# 03_PCM5102A.net
KiCad netlist of a schematic drawn in Altium Designer
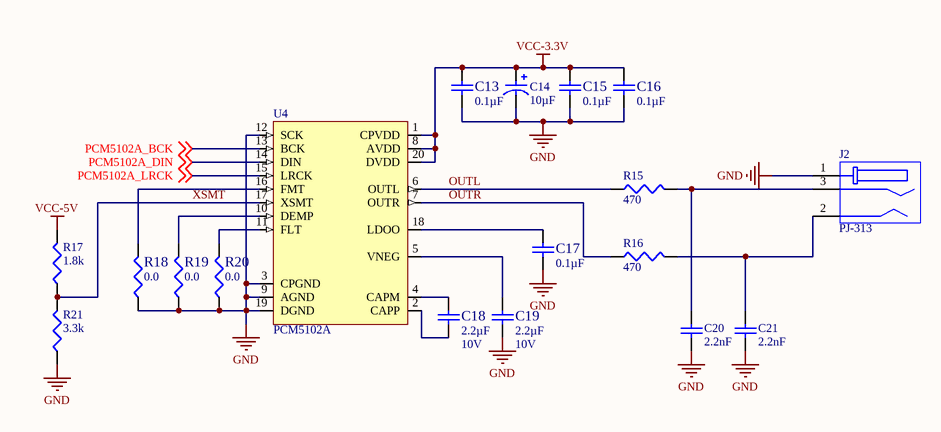
[diagram p0: 03_PCM5102A.SchDoc]

(export (version "E")
  (design (tool "Eeschema 10.0.6"))
  (components
    (comp (ref "C13")
      (value "CC0603KRX7R9BB104")
      (footprint "RAD-0.1")
      (description "CAP CER 0.1UF 50V 10% X7R 0603")
      (fields
        (field (name "MANUFACTURER") "Yageo")
        (field (name "TOLERANCE") "±10%")
        (field (name "CAPACITANCE") "0.1µF")
      )
      (libsource (lib "SEAL_Capacitors_0603") (part "CC0603KRX7R9BB104"))
    )
    (comp (ref "C14")
      (value "EEE-1HA100WR")
      (footprint "RB2-5")
      (description "CAP ALUM 10UF 50V 20% SMD")
      (fields
        (field (name "MANUFACTURER") "Panasonic Electronic Components")
        (field (name "TOLERANCE") "±20%")
        (field (name "CAPACITANCE") "10µF")
      )
      (libsource (lib "DSS_Passives") (part "EEE-1HA100WR"))
    )
    (comp (ref "C15")
      (value "CC0603KRX7R9BB104")
      (footprint "RAD-0.1")
      (description "CAP CER 0.1UF 50V 10% X7R 0603")
      (fields
        (field (name "MANUFACTURER") "Yageo")
        (field (name "TOLERANCE") "±10%")
        (field (name "CAPACITANCE") "0.1µF")
      )
      (libsource (lib "SEAL_Capacitors_0603") (part "CC0603KRX7R9BB104"))
    )
    (comp (ref "C16")
      (value "CC0603KRX7R9BB104")
      (footprint "RAD-0.1")
      (description "CAP CER 0.1UF 50V 10% X7R 0603")
      (fields
        (field (name "MANUFACTURER") "Yageo")
        (field (name "TOLERANCE") "±10%")
        (field (name "CAPACITANCE") "0.1µF")
      )
      (libsource (lib "SEAL_Capacitors_0603") (part "CC0603KRX7R9BB104"))
    )
    (comp (ref "C17")
      (value "CC0603KRX7R9BB104")
      (footprint "RAD-0.1")
      (description "CAP CER 0.1UF 50V 10% X7R 0603")
      (fields
        (field (name "MANUFACTURER") "Yageo")
        (field (name "TOLERANCE") "±10%")
        (field (name "CAPACITANCE") "0.1µF")
      )
      (libsource (lib "SEAL_Capacitors_0603") (part "CC0603KRX7R9BB104"))
    )
    (comp (ref "C18")
      (value "LMK107B7225KA-T")
      (footprint "RB2-5")
      (description "CAP CER 2.2UF 10V 10% X7R 0603")
      (fields
        (field (name "MANUFACTURER") "Taiyo Yuden")
        (field (name "TOLERANCE") "±10%")
        (field (name "CAPACITANCE") "2.2µF")
        (field (name "VOLTAGE - RATED") "10V")
      )
      (libsource (lib "SEAL_Capacitors_0603") (part "LMK107B7225KA-T"))
    )
    (comp (ref "C19")
      (value "LMK107B7225KA-T")
      (footprint "RB2-5")
      (description "CAP CER 2.2UF 10V 10% X7R 0603")
      (fields
        (field (name "MANUFACTURER") "Taiyo Yuden")
        (field (name "TOLERANCE") "±10%")
        (field (name "CAPACITANCE") "2.2µF")
        (field (name "VOLTAGE - RATED") "10V")
      )
      (libsource (lib "SEAL_Capacitors_0603") (part "LMK107B7225KA-T"))
    )
    (comp (ref "C20")
      (value "2.2nF")
      (footprint "RAD-0.1")
      (description "CAP CER 2200PF 50V 10% X7R 0603")
      (fields
        (field (name "MANUFACTURER") "Kemet")
        (field (name "MANUFACTURER PART NUMBER") "C0603C222K5RACTU")
      )
      (libsource (lib "SEAL_Capacitors_0603") (part "C0603C222K5RACTU"))
    )
    (comp (ref "C21")
      (value "2.2nF")
      (footprint "RAD-0.1")
      (description "CAP CER 2200PF 50V 10% X7R 0603")
      (fields
        (field (name "MANUFACTURER") "Kemet")
        (field (name "MANUFACTURER PART NUMBER") "C0603C222K5RACTU")
      )
      (libsource (lib "SEAL_Capacitors_0603") (part "C0603C222K5RACTU"))
    )
    (comp (ref "J2")
      (value "PJ-313")
      (footprint "PJ-313")
      (description "3.5mm Audio Jack")
      (libsource (lib "Miscellaneous Modules") (part "PJ-313"))
    )
    (comp (ref "R15")
      (value "ERJ-3EKF4700V")
      (footprint "AXIAL-0.3")
      (description "RES 470 OHM 1% 1/10W 0603 SMD")
      (fields
        (field (name "MANUFACTURER") "Panasonic Electronic Components")
        (field (name "TOLERANCE") "±1%")
        (field (name "RESISTANCE (OHMS)") "470")
      )
      (libsource (lib "SEAL_Resistors_0603") (part "ERJ-3EKF4700V"))
    )
    (comp (ref "R16")
      (value "ERJ-3EKF4700V")
      (footprint "AXIAL-0.3")
      (description "RES 470 OHM 1% 1/10W 0603 SMD")
      (fields
        (field (name "MANUFACTURER") "Panasonic Electronic Components")
        (field (name "TOLERANCE") "±1%")
        (field (name "RESISTANCE (OHMS)") "470")
      )
      (libsource (lib "SEAL_Resistors_0603") (part "ERJ-3EKF4700V"))
    )
    (comp (ref "R17")
      (value "ERJ-3GEYJ182V")
      (footprint "AXIAL-0.3")
      (description "RES 1.8K OHM 1/10W 5% 0603 SMD")
      (fields
        (field (name "MANUFACTURER") "Panasonic Electronic Components")
        (field (name "TOLERANCE") "±5%")
        (field (name "RESISTANCE (OHMS)") "1.8k")
      )
      (libsource (lib "SEAL_Resistors_0603") (part "ERJ-3GEYJ182V"))
    )
    (comp (ref "R18")
      (value "RC0603JR-070RL")
      (footprint "AXIAL-0.3")
      (description "RES 0.0 OHM 1/10W 0603 SMD")
      (fields
        (field (name "MANUFACTURER") "Yageo")
        (field (name "TOLERANCE") "Jumper")
        (field (name "RESISTANCE (OHMS)") "0.0")
      )
      (libsource (lib "SEAL_Resistors_0603") (part "RC0603JR-070RL"))
    )
    (comp (ref "R19")
      (value "RC0603JR-070RL")
      (footprint "AXIAL-0.3")
      (description "RES 0.0 OHM 1/10W 0603 SMD")
      (fields
        (field (name "MANUFACTURER") "Yageo")
        (field (name "TOLERANCE") "Jumper")
        (field (name "RESISTANCE (OHMS)") "0.0")
      )
      (libsource (lib "SEAL_Resistors_0603") (part "RC0603JR-070RL"))
    )
    (comp (ref "R20")
      (value "RC0603JR-070RL")
      (footprint "AXIAL-0.3")
      (description "RES 0.0 OHM 1/10W 0603 SMD")
      (fields
        (field (name "MANUFACTURER") "Yageo")
        (field (name "TOLERANCE") "Jumper")
        (field (name "RESISTANCE (OHMS)") "0.0")
      )
      (libsource (lib "SEAL_Resistors_0603") (part "RC0603JR-070RL"))
    )
    (comp (ref "R21")
      (value "ERJ-3GEYJ332V")
      (footprint "AXIAL-0.3")
      (description "RES 3.3K OHM 5% 1/10W 0603 SMD")
      (fields
        (field (name "MANUFACTURER") "Panasonic Electronic Components")
        (field (name "TOLERANCE") "±5%")
        (field (name "RESISTANCE (OHMS)") "3.3k")
      )
      (libsource (lib "SEAL_Resistors_0603") (part "ERJ-3GEYJ332V"))
    )
    (comp (ref "U4")
      (value "PCM5102A")
      (footprint "TSSOP-20-1")
      (description "IC DAC 16/24/32BIT SRL 20TSSOP")
      (fields
        (field (name "MANUFACTURER") "Texas Instruments")
        (field (name "MANUFACTURER PART NUMBER") "PCM5102APWR")
      )
      (libsource (lib "DSS_DigitalIC") (part "PCM5102APWR"))
    )
  )
  (nets
    (net (code "1") (name "/OUTL") (class "Default")
      (node (ref "R15") (pin "1") (pinfunction "1_1") (pintype "passive"))
      (node (ref "U4") (pin "6") (pinfunction "OUTL_6") (pintype "output"))
    )
    (net (code "2") (name "/OUTR") (class "Default")
      (node (ref "R16") (pin "1") (pinfunction "1_1") (pintype "passive"))
      (node (ref "U4") (pin "7") (pinfunction "OUTR_7") (pintype "output"))
    )
    (net (code "3") (name "/XSMT") (class "Default")
      (node (ref "R17") (pin "1") (pinfunction "1_1") (pintype "passive"))
      (node (ref "R21") (pin "2") (pinfunction "2_2") (pintype "passive"))
      (node (ref "U4") (pin "17") (pinfunction "XSMT_17") (pintype "input"))
    )
    (net (code "4") (name "GND") (class "Default")
      (node (ref "C13") (pin "2") (pinfunction "2_2") (pintype "passive"))
      (node (ref "C14") (pin "2") (pinfunction "Anode_2") (pintype "passive"))
      (node (ref "C15") (pin "2") (pinfunction "2_2") (pintype "passive"))
      (node (ref "C16") (pin "2") (pinfunction "2_2") (pintype "passive"))
      (node (ref "C17") (pin "2") (pinfunction "2_2") (pintype "passive"))
      (node (ref "C19") (pin "2") (pinfunction "2_2") (pintype "passive"))
      (node (ref "C20") (pin "2") (pinfunction "2_2") (pintype "passive"))
      (node (ref "C21") (pin "2") (pinfunction "2_2") (pintype "passive"))
      (node (ref "J2") (pin "1") (pinfunction "1_1") (pintype "passive"))
      (node (ref "R18") (pin "1") (pinfunction "1_1") (pintype "passive"))
      (node (ref "R19") (pin "1") (pinfunction "1_1") (pintype "passive"))
      (node (ref "R20") (pin "1") (pinfunction "1_1") (pintype "passive"))
      (node (ref "R21") (pin "1") (pinfunction "1_1") (pintype "passive"))
      (node (ref "U4") (pin "12") (pinfunction "SCK_12") (pintype "input"))
      (node (ref "U4") (pin "19") (pinfunction "DGND_19") (pintype "passive"))
      (node (ref "U4") (pin "3") (pinfunction "CPGND_3") (pintype "passive"))
      (node (ref "U4") (pin "9") (pinfunction "AGND_9") (pintype "passive"))
    )
    (net (code "5") (name "Net-(C20-Pad1)") (class "Default")
      (node (ref "C20") (pin "1") (pinfunction "1_1") (pintype "passive"))
      (node (ref "J2") (pin "3") (pinfunction "3_3") (pintype "passive"))
      (node (ref "R15") (pin "2") (pinfunction "2_2") (pintype "passive"))
    )
    (net (code "6") (name "Net-(C21-Pad1)") (class "Default")
      (node (ref "C21") (pin "1") (pinfunction "1_1") (pintype "passive"))
      (node (ref "J2") (pin "2") (pinfunction "2_2") (pintype "passive"))
      (node (ref "R16") (pin "2") (pinfunction "2_2") (pintype "passive"))
    )
    (net (code "7") (name "Net-(U4-CAPM)") (class "Default")
      (node (ref "C18") (pin "1") (pinfunction "1_1") (pintype "passive"))
      (node (ref "U4") (pin "4") (pinfunction "CAPM_4") (pintype "passive"))
    )
    (net (code "8") (name "Net-(U4-CAPP)") (class "Default")
      (node (ref "C18") (pin "2") (pinfunction "2_2") (pintype "passive"))
      (node (ref "U4") (pin "2") (pinfunction "CAPP_2") (pintype "passive"))
    )
    (net (code "9") (name "Net-(U4-DEMP)") (class "Default")
      (node (ref "R19") (pin "2") (pinfunction "2_2") (pintype "passive"))
      (node (ref "U4") (pin "10") (pinfunction "DEMP_10") (pintype "input"))
    )
    (net (code "10") (name "Net-(U4-FLT)") (class "Default")
      (node (ref "R20") (pin "2") (pinfunction "2_2") (pintype "passive"))
      (node (ref "U4") (pin "11") (pinfunction "FLT_11") (pintype "input"))
    )
    (net (code "11") (name "Net-(U4-FMT)") (class "Default")
      (node (ref "R18") (pin "2") (pinfunction "2_2") (pintype "passive"))
      (node (ref "U4") (pin "16") (pinfunction "FMT_16") (pintype "input"))
    )
    (net (code "12") (name "Net-(U4-LDOO)") (class "Default")
      (node (ref "C17") (pin "1") (pinfunction "1_1") (pintype "passive"))
      (node (ref "U4") (pin "18") (pinfunction "LDOO_18") (pintype "passive"))
    )
    (net (code "13") (name "Net-(U4-VNEG)") (class "Default")
      (node (ref "C19") (pin "1") (pinfunction "1_1") (pintype "passive"))
      (node (ref "U4") (pin "5") (pinfunction "VNEG_5") (pintype "passive"))
    )
    (net (code "14") (name "PCM5102A_BCK") (class "Default")
      (node (ref "U4") (pin "13") (pinfunction "BCK_13") (pintype "input"))
    )
    (net (code "15") (name "PCM5102A_DIN") (class "Default")
      (node (ref "U4") (pin "14") (pinfunction "DIN_14") (pintype "input"))
    )
    (net (code "16") (name "PCM5102A_LRCK") (class "Default")
      (node (ref "U4") (pin "15") (pinfunction "LRCK_15") (pintype "input"))
    )
    (net (code "17") (name "VCC-3.3V") (class "Default")
      (node (ref "C13") (pin "1") (pinfunction "1_1") (pintype "passive"))
      (node (ref "C14") (pin "1") (pinfunction "Cathode_1") (pintype "passive"))
      (node (ref "C15") (pin "1") (pinfunction "1_1") (pintype "passive"))
      (node (ref "C16") (pin "1") (pinfunction "1_1") (pintype "passive"))
      (node (ref "U4") (pin "1") (pinfunction "CPVDD_1") (pintype "passive"))
      (node (ref "U4") (pin "20") (pinfunction "DVDD_20") (pintype "passive"))
      (node (ref "U4") (pin "8") (pinfunction "AVDD_8") (pintype "passive"))
    )
    (net (code "18") (name "VCC-5V") (class "Default")
      (node (ref "R17") (pin "2") (pinfunction "2_2") (pintype "passive"))
    )
  )
)
